# board.net
KiCad netlist of a schematic drawn in EAGLE
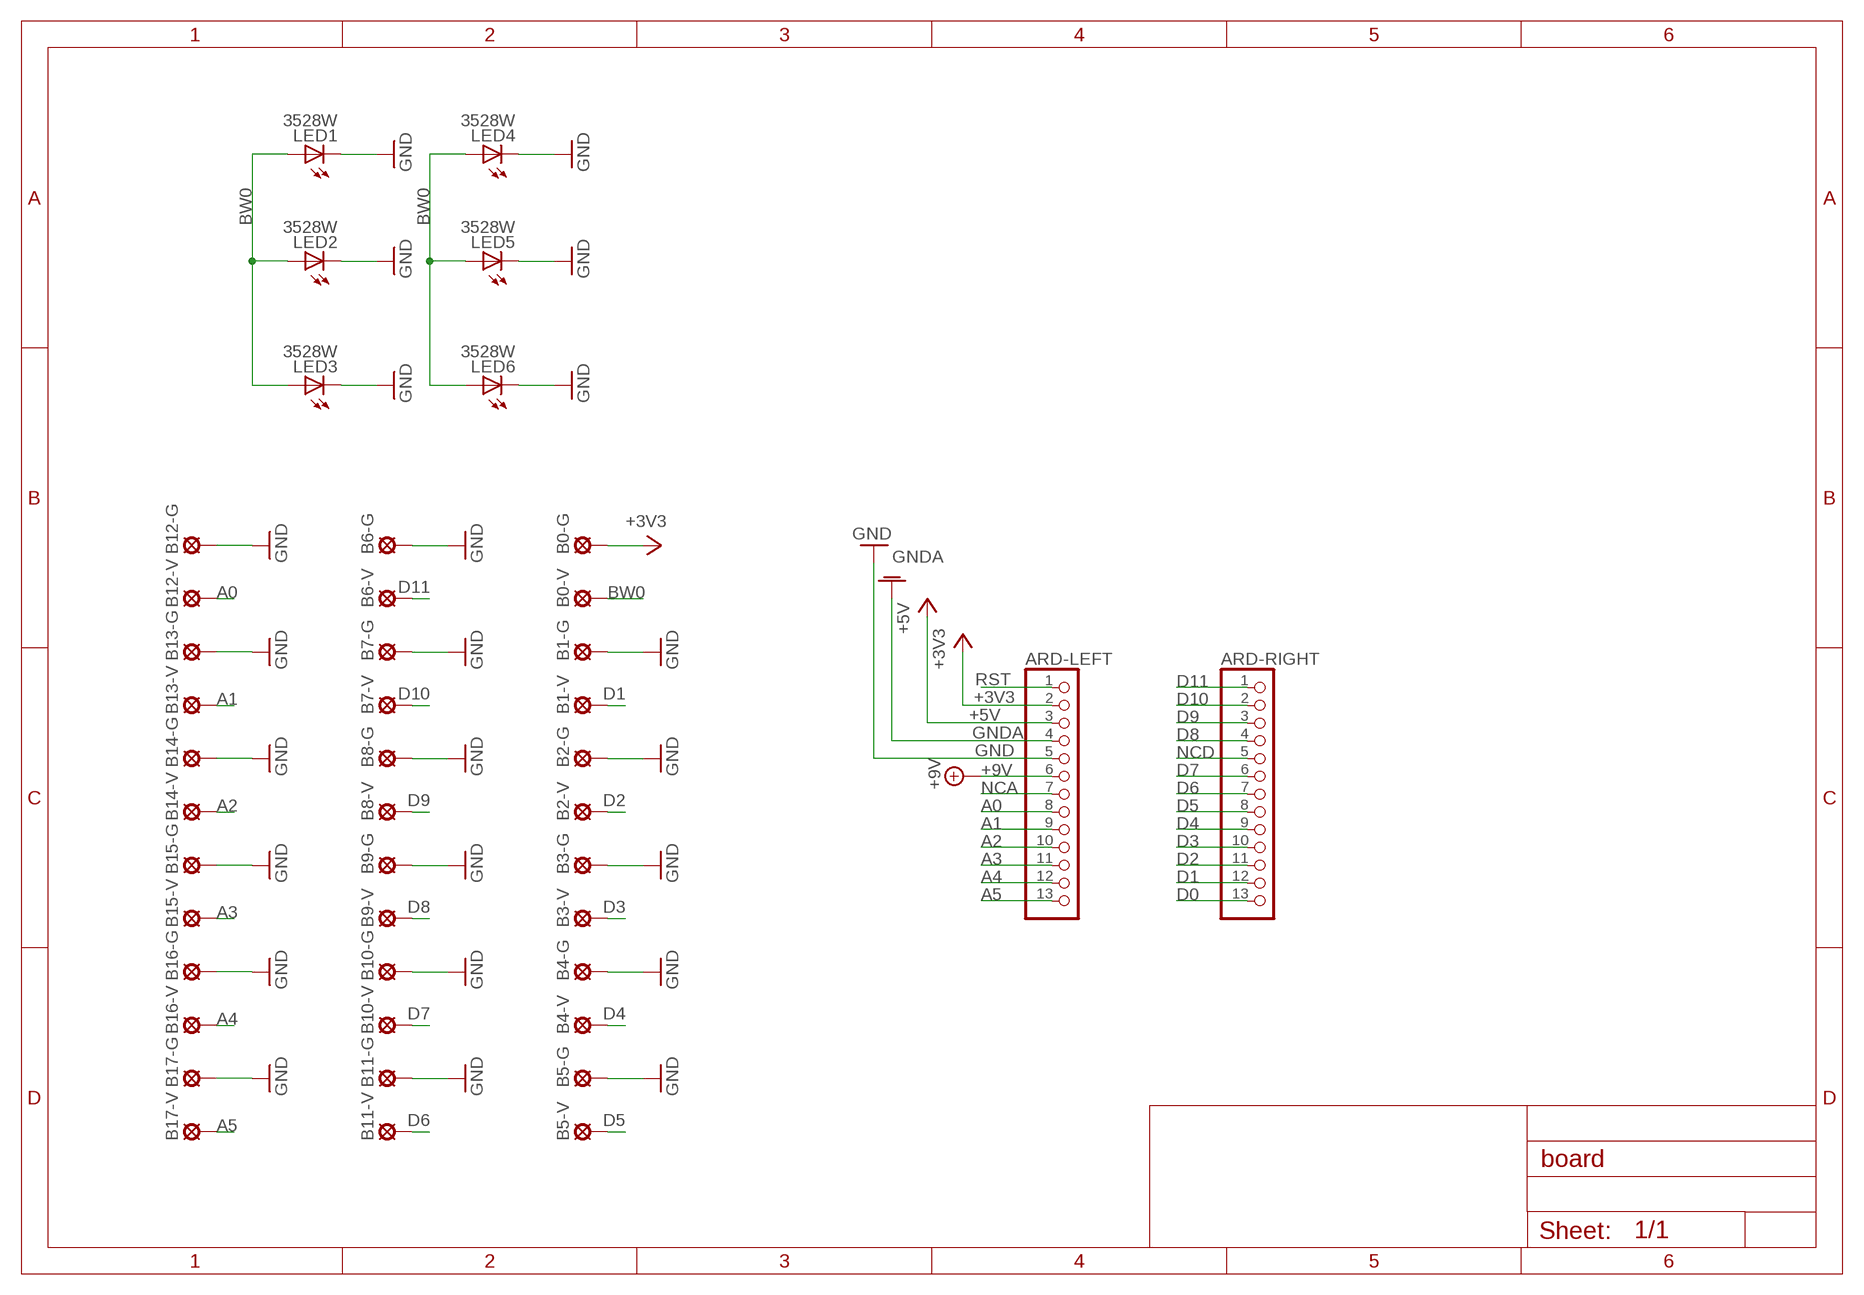
[diagram p0: schematic, sheet 1]

(export (version "E")
  (design (tool "Eeschema 10.0.6"))
  (components
    (comp (ref "ARD-LEFT")
      (value "PINHD-1X13")
      (footprint "eagle-import:1X13")
      (libsource (lib "eagle-import") (part "PINHD-1X13"))
    )
    (comp (ref "ARD-RIGHT")
      (value "PINHD-1X13")
      (footprint "eagle-import:1X13")
      (libsource (lib "eagle-import") (part "PINHD-1X13"))
    )
    (comp (ref "B0-G")
      (value "LSP10")
      (footprint "eagle-import:LSP10")
      (libsource (lib "eagle-import") (part "LSP10"))
    )
    (comp (ref "B0-V")
      (value "LSP10")
      (footprint "eagle-import:LSP10")
      (libsource (lib "eagle-import") (part "LSP10"))
    )
    (comp (ref "B1-G")
      (value "LSP10")
      (footprint "eagle-import:LSP10")
      (libsource (lib "eagle-import") (part "LSP10"))
    )
    (comp (ref "B1-V")
      (value "LSP10")
      (footprint "eagle-import:LSP10")
      (libsource (lib "eagle-import") (part "LSP10"))
    )
    (comp (ref "B2-G")
      (value "LSP10")
      (footprint "eagle-import:LSP10")
      (libsource (lib "eagle-import") (part "LSP10"))
    )
    (comp (ref "B2-V")
      (value "LSP10")
      (footprint "eagle-import:LSP10")
      (libsource (lib "eagle-import") (part "LSP10"))
    )
    (comp (ref "B3-G")
      (value "LSP10")
      (footprint "eagle-import:LSP10")
      (libsource (lib "eagle-import") (part "LSP10"))
    )
    (comp (ref "B3-V")
      (value "LSP10")
      (footprint "eagle-import:LSP10")
      (libsource (lib "eagle-import") (part "LSP10"))
    )
    (comp (ref "B4-G")
      (value "LSP10")
      (footprint "eagle-import:LSP10")
      (libsource (lib "eagle-import") (part "LSP10"))
    )
    (comp (ref "B4-V")
      (value "LSP10")
      (footprint "eagle-import:LSP10")
      (libsource (lib "eagle-import") (part "LSP10"))
    )
    (comp (ref "B5-G")
      (value "LSP10")
      (footprint "eagle-import:LSP10")
      (libsource (lib "eagle-import") (part "LSP10"))
    )
    (comp (ref "B5-V")
      (value "LSP10")
      (footprint "eagle-import:LSP10")
      (libsource (lib "eagle-import") (part "LSP10"))
    )
    (comp (ref "B6-G")
      (value "LSP10")
      (footprint "eagle-import:LSP10")
      (libsource (lib "eagle-import") (part "LSP10"))
    )
    (comp (ref "B6-V")
      (value "LSP10")
      (footprint "eagle-import:LSP10")
      (libsource (lib "eagle-import") (part "LSP10"))
    )
    (comp (ref "B7-G")
      (value "LSP10")
      (footprint "eagle-import:LSP10")
      (libsource (lib "eagle-import") (part "LSP10"))
    )
    (comp (ref "B7-V")
      (value "LSP10")
      (footprint "eagle-import:LSP10")
      (libsource (lib "eagle-import") (part "LSP10"))
    )
    (comp (ref "B8-G")
      (value "LSP10")
      (footprint "eagle-import:LSP10")
      (libsource (lib "eagle-import") (part "LSP10"))
    )
    (comp (ref "B8-V")
      (value "LSP10")
      (footprint "eagle-import:LSP10")
      (libsource (lib "eagle-import") (part "LSP10"))
    )
    (comp (ref "B9-G")
      (value "LSP10")
      (footprint "eagle-import:LSP10")
      (libsource (lib "eagle-import") (part "LSP10"))
    )
    (comp (ref "B9-V")
      (value "LSP10")
      (footprint "eagle-import:LSP10")
      (libsource (lib "eagle-import") (part "LSP10"))
    )
    (comp (ref "B10-G")
      (value "LSP10")
      (footprint "eagle-import:LSP10")
      (libsource (lib "eagle-import") (part "LSP10"))
    )
    (comp (ref "B10-V")
      (value "LSP10")
      (footprint "eagle-import:LSP10")
      (libsource (lib "eagle-import") (part "LSP10"))
    )
    (comp (ref "B11-G")
      (value "LSP10")
      (footprint "eagle-import:LSP10")
      (libsource (lib "eagle-import") (part "LSP10"))
    )
    (comp (ref "B11-V")
      (value "LSP10")
      (footprint "eagle-import:LSP10")
      (libsource (lib "eagle-import") (part "LSP10"))
    )
    (comp (ref "B12-G")
      (value "LSP10")
      (footprint "eagle-import:LSP10")
      (libsource (lib "eagle-import") (part "LSP10"))
    )
    (comp (ref "B12-V")
      (value "LSP10")
      (footprint "eagle-import:LSP10")
      (libsource (lib "eagle-import") (part "LSP10"))
    )
    (comp (ref "B13-G")
      (value "LSP10")
      (footprint "eagle-import:LSP10")
      (libsource (lib "eagle-import") (part "LSP10"))
    )
    (comp (ref "B13-V")
      (value "LSP10")
      (footprint "eagle-import:LSP10")
      (libsource (lib "eagle-import") (part "LSP10"))
    )
    (comp (ref "B14-G")
      (value "LSP10")
      (footprint "eagle-import:LSP10")
      (libsource (lib "eagle-import") (part "LSP10"))
    )
    (comp (ref "B14-V")
      (value "LSP10")
      (footprint "eagle-import:LSP10")
      (libsource (lib "eagle-import") (part "LSP10"))
    )
    (comp (ref "B15-G")
      (value "LSP10")
      (footprint "eagle-import:LSP10")
      (libsource (lib "eagle-import") (part "LSP10"))
    )
    (comp (ref "B15-V")
      (value "LSP10")
      (footprint "eagle-import:LSP10")
      (libsource (lib "eagle-import") (part "LSP10"))
    )
    (comp (ref "B16-G")
      (value "LSP10")
      (footprint "eagle-import:LSP10")
      (libsource (lib "eagle-import") (part "LSP10"))
    )
    (comp (ref "B16-V")
      (value "LSP10")
      (footprint "eagle-import:LSP10")
      (libsource (lib "eagle-import") (part "LSP10"))
    )
    (comp (ref "B17-G")
      (value "LSP10")
      (footprint "eagle-import:LSP10")
      (libsource (lib "eagle-import") (part "LSP10"))
    )
    (comp (ref "B17-V")
      (value "LSP10")
      (footprint "eagle-import:LSP10")
      (libsource (lib "eagle-import") (part "LSP10"))
    )
    (comp (ref "LED1")
      (value "3528W")
      (footprint "eagle-import:P-LCC-2")
      (libsource (lib "eagle-import") (part "LEDP-LCC-2"))
    )
    (comp (ref "LED2")
      (value "3528W")
      (footprint "eagle-import:P-LCC-2")
      (libsource (lib "eagle-import") (part "LEDP-LCC-2"))
    )
    (comp (ref "LED3")
      (value "3528W")
      (footprint "eagle-import:P-LCC-2")
      (libsource (lib "eagle-import") (part "LEDP-LCC-2"))
    )
    (comp (ref "LED4")
      (value "3528W")
      (footprint "eagle-import:P-LCC-2")
      (libsource (lib "eagle-import") (part "LEDP-LCC-2"))
    )
    (comp (ref "LED5")
      (value "3528W")
      (footprint "eagle-import:P-LCC-2")
      (libsource (lib "eagle-import") (part "LEDP-LCC-2"))
    )
    (comp (ref "LED6")
      (value "3528W")
      (footprint "eagle-import:P-LCC-2")
      (libsource (lib "eagle-import") (part "LEDP-LCC-2"))
    )
  )
  (nets
    (net (code "1") (name "+3V3") (class "Default")
      (node (ref "ARD-LEFT") (pin "2") (pinfunction "2_2") (pintype "passive"))
      (node (ref "B0-G") (pin "MP") (pinfunction "MP_MP") (pintype "passive"))
    )
    (net (code "2") (name "+5V") (class "Default")
      (node (ref "ARD-LEFT") (pin "3") (pinfunction "3_3") (pintype "passive"))
    )
    (net (code "3") (name "+9V") (class "Default")
      (node (ref "ARD-LEFT") (pin "6") (pinfunction "6_6") (pintype "passive"))
    )
    (net (code "4") (name "/A0") (class "Default")
      (node (ref "ARD-LEFT") (pin "8") (pinfunction "8_8") (pintype "passive"))
      (node (ref "B12-V") (pin "MP") (pinfunction "MP_MP") (pintype "passive"))
    )
    (net (code "5") (name "/A1") (class "Default")
      (node (ref "ARD-LEFT") (pin "9") (pinfunction "9_9") (pintype "passive"))
      (node (ref "B13-V") (pin "MP") (pinfunction "MP_MP") (pintype "passive"))
    )
    (net (code "6") (name "/A2") (class "Default")
      (node (ref "ARD-LEFT") (pin "10") (pinfunction "10_10") (pintype "passive"))
      (node (ref "B14-V") (pin "MP") (pinfunction "MP_MP") (pintype "passive"))
    )
    (net (code "7") (name "/A3") (class "Default")
      (node (ref "ARD-LEFT") (pin "11") (pinfunction "11_11") (pintype "passive"))
      (node (ref "B15-V") (pin "MP") (pinfunction "MP_MP") (pintype "passive"))
    )
    (net (code "8") (name "/A4") (class "Default")
      (node (ref "ARD-LEFT") (pin "12") (pinfunction "12_12") (pintype "passive"))
      (node (ref "B16-V") (pin "MP") (pinfunction "MP_MP") (pintype "passive"))
    )
    (net (code "9") (name "/A5") (class "Default")
      (node (ref "ARD-LEFT") (pin "13") (pinfunction "13_13") (pintype "passive"))
      (node (ref "B17-V") (pin "MP") (pinfunction "MP_MP") (pintype "passive"))
    )
    (net (code "10") (name "/BW0") (class "Default")
      (node (ref "B0-V") (pin "MP") (pinfunction "MP_MP") (pintype "passive"))
      (node (ref "LED1") (pin "A") (pinfunction "A_A") (pintype "passive"))
      (node (ref "LED2") (pin "A") (pinfunction "A_A") (pintype "passive"))
      (node (ref "LED3") (pin "A") (pinfunction "A_A") (pintype "passive"))
      (node (ref "LED4") (pin "A") (pinfunction "A_A") (pintype "passive"))
      (node (ref "LED5") (pin "A") (pinfunction "A_A") (pintype "passive"))
      (node (ref "LED6") (pin "A") (pinfunction "A_A") (pintype "passive"))
    )
    (net (code "11") (name "/D0") (class "Default")
      (node (ref "ARD-RIGHT") (pin "13") (pinfunction "13_13") (pintype "passive"))
    )
    (net (code "12") (name "/D1") (class "Default")
      (node (ref "ARD-RIGHT") (pin "12") (pinfunction "12_12") (pintype "passive"))
      (node (ref "B1-V") (pin "MP") (pinfunction "MP_MP") (pintype "passive"))
    )
    (net (code "13") (name "/D2") (class "Default")
      (node (ref "ARD-RIGHT") (pin "11") (pinfunction "11_11") (pintype "passive"))
      (node (ref "B2-V") (pin "MP") (pinfunction "MP_MP") (pintype "passive"))
    )
    (net (code "14") (name "/D3") (class "Default")
      (node (ref "ARD-RIGHT") (pin "10") (pinfunction "10_10") (pintype "passive"))
      (node (ref "B3-V") (pin "MP") (pinfunction "MP_MP") (pintype "passive"))
    )
    (net (code "15") (name "/D4") (class "Default")
      (node (ref "ARD-RIGHT") (pin "9") (pinfunction "9_9") (pintype "passive"))
      (node (ref "B4-V") (pin "MP") (pinfunction "MP_MP") (pintype "passive"))
    )
    (net (code "16") (name "/D5") (class "Default")
      (node (ref "ARD-RIGHT") (pin "8") (pinfunction "8_8") (pintype "passive"))
      (node (ref "B5-V") (pin "MP") (pinfunction "MP_MP") (pintype "passive"))
    )
    (net (code "17") (name "/D6") (class "Default")
      (node (ref "ARD-RIGHT") (pin "7") (pinfunction "7_7") (pintype "passive"))
      (node (ref "B11-V") (pin "MP") (pinfunction "MP_MP") (pintype "passive"))
    )
    (net (code "18") (name "/D7") (class "Default")
      (node (ref "ARD-RIGHT") (pin "6") (pinfunction "6_6") (pintype "passive"))
      (node (ref "B10-V") (pin "MP") (pinfunction "MP_MP") (pintype "passive"))
    )
    (net (code "19") (name "/D8") (class "Default")
      (node (ref "ARD-RIGHT") (pin "4") (pinfunction "4_4") (pintype "passive"))
      (node (ref "B9-V") (pin "MP") (pinfunction "MP_MP") (pintype "passive"))
    )
    (net (code "20") (name "/D9") (class "Default")
      (node (ref "ARD-RIGHT") (pin "3") (pinfunction "3_3") (pintype "passive"))
      (node (ref "B8-V") (pin "MP") (pinfunction "MP_MP") (pintype "passive"))
    )
    (net (code "21") (name "/D10") (class "Default")
      (node (ref "ARD-RIGHT") (pin "2") (pinfunction "2_2") (pintype "passive"))
      (node (ref "B7-V") (pin "MP") (pinfunction "MP_MP") (pintype "passive"))
    )
    (net (code "22") (name "/D11") (class "Default")
      (node (ref "ARD-RIGHT") (pin "1") (pinfunction "1_1") (pintype "passive"))
      (node (ref "B6-V") (pin "MP") (pinfunction "MP_MP") (pintype "passive"))
    )
    (net (code "23") (name "/NCA") (class "Default")
      (node (ref "ARD-LEFT") (pin "7") (pinfunction "7_7") (pintype "passive"))
    )
    (net (code "24") (name "/NCD") (class "Default")
      (node (ref "ARD-RIGHT") (pin "5") (pinfunction "5_5") (pintype "passive"))
    )
    (net (code "25") (name "/RST") (class "Default")
      (node (ref "ARD-LEFT") (pin "1") (pinfunction "1_1") (pintype "passive"))
    )
    (net (code "26") (name "GND") (class "Default")
      (node (ref "ARD-LEFT") (pin "5") (pinfunction "5_5") (pintype "passive"))
      (node (ref "B1-G") (pin "MP") (pinfunction "MP_MP") (pintype "passive"))
      (node (ref "B10-G") (pin "MP") (pinfunction "MP_MP") (pintype "passive"))
      (node (ref "B11-G") (pin "MP") (pinfunction "MP_MP") (pintype "passive"))
      (node (ref "B12-G") (pin "MP") (pinfunction "MP_MP") (pintype "passive"))
      (node (ref "B13-G") (pin "MP") (pinfunction "MP_MP") (pintype "passive"))
      (node (ref "B14-G") (pin "MP") (pinfunction "MP_MP") (pintype "passive"))
      (node (ref "B15-G") (pin "MP") (pinfunction "MP_MP") (pintype "passive"))
      (node (ref "B16-G") (pin "MP") (pinfunction "MP_MP") (pintype "passive"))
      (node (ref "B17-G") (pin "MP") (pinfunction "MP_MP") (pintype "passive"))
      (node (ref "B2-G") (pin "MP") (pinfunction "MP_MP") (pintype "passive"))
      (node (ref "B3-G") (pin "MP") (pinfunction "MP_MP") (pintype "passive"))
      (node (ref "B4-G") (pin "MP") (pinfunction "MP_MP") (pintype "passive"))
      (node (ref "B5-G") (pin "MP") (pinfunction "MP_MP") (pintype "passive"))
      (node (ref "B6-G") (pin "MP") (pinfunction "MP_MP") (pintype "passive"))
      (node (ref "B7-G") (pin "MP") (pinfunction "MP_MP") (pintype "passive"))
      (node (ref "B8-G") (pin "MP") (pinfunction "MP_MP") (pintype "passive"))
      (node (ref "B9-G") (pin "MP") (pinfunction "MP_MP") (pintype "passive"))
      (node (ref "LED1") (pin "C") (pinfunction "C_C") (pintype "passive"))
      (node (ref "LED2") (pin "C") (pinfunction "C_C") (pintype "passive"))
      (node (ref "LED3") (pin "C") (pinfunction "C_C") (pintype "passive"))
      (node (ref "LED4") (pin "C") (pinfunction "C_C") (pintype "passive"))
      (node (ref "LED5") (pin "C") (pinfunction "C_C") (pintype "passive"))
      (node (ref "LED6") (pin "C") (pinfunction "C_C") (pintype "passive"))
    )
    (net (code "27") (name "GNDA") (class "Default")
      (node (ref "ARD-LEFT") (pin "4") (pinfunction "4_4") (pintype "passive"))
    )
  )
)
